# Power.net
KiCad netlist of a schematic drawn in Altium Designer
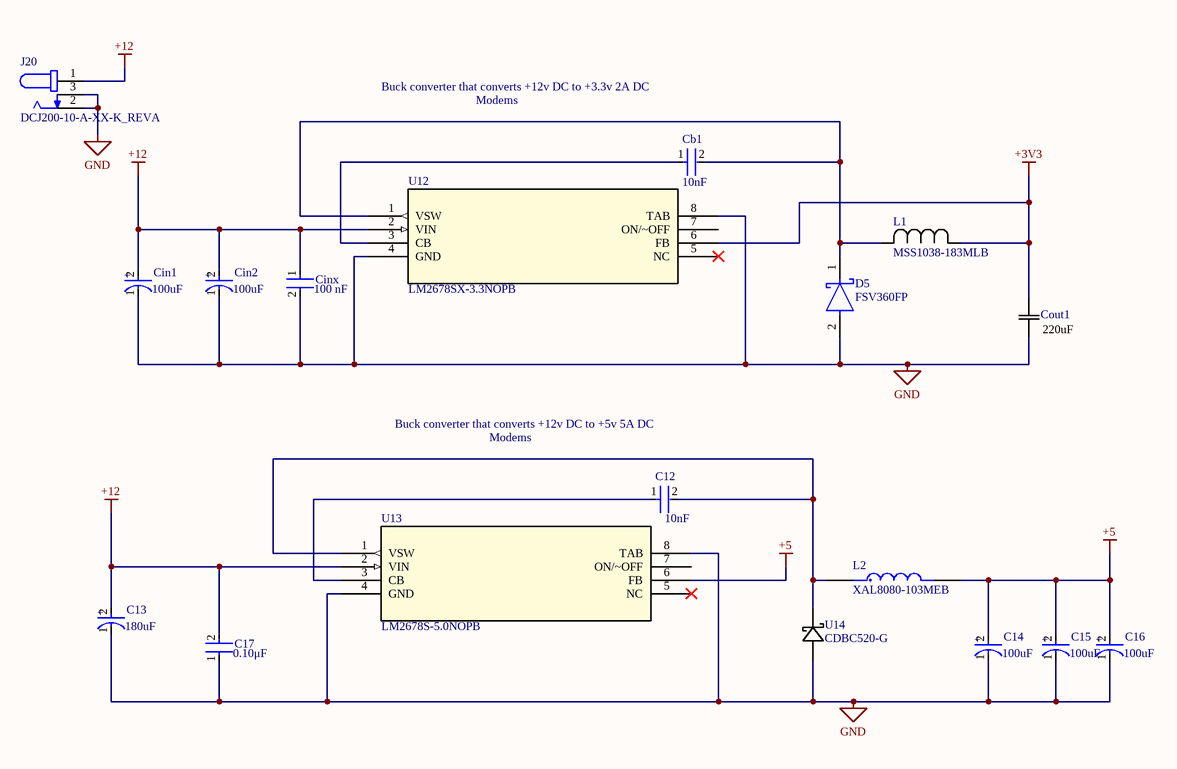
[diagram p0: Power.SchDoc]

(export (version "E")
  (design (tool "Eeschema 10.0.6"))
  (components
    (comp (ref "C12")
      (value "CGA4C2C0G1H103J060AA")
      (footprint "FP-CGA4J-IPC_B")
      (description "Cap Ceramic 10nF 50V C0G 5% Pad SMD 0805 +125°C Automotive T/R")
      (fields (field (name "CAPACITANCE") "10nF") (field (name "TOLERANCE") "5%"))
      (libsource (lib "Altium Content Vault") (part "b4654b650e69147ec39a6b967a45e02"))
    )
    (comp (ref "C13")
      (value "20SVPF180M")
      (footprint "FP-OS-CON-SMT-E7-MFG")
      (description "Conductive Polymer Aluminum Solid Capacitors (OS-CON) 180uF ±20% 20V RADIAL SMT 8x6.9mm")
      (fields
        (field (name "VOLTAGE") "20V")
        (field (name "CAPACITANCE") "180uF")
        (field (name "TOLERANCE") "20%")
      )
      (libsource (lib "Altium Content Vault") (part "cf48714ba7e38822c1575c7ec0b6d1f"))
    )
    (comp (ref "C14")
      (value "8TPE100MAZB")
      (footprint "FP-POSCAP-B2-MFG")
      (description "Molded Tantalum Polymer Capacitor 100uF 20% 8V life 1000Hours SMD 1411")
      (fields
        (field (name "TOLERANCE") "20%")
        (field (name "CAPACITANCE") "100uF")
        (field (name "VOLTAGE") "8V")
      )
      (libsource (lib "Altium Content Vault") (part "cf48714ba7e38822c1575c7ec0b6d1f"))
    )
    (comp (ref "C15")
      (value "8TPE100MAZB")
      (footprint "FP-POSCAP-B2-MFG")
      (description "Molded Tantalum Polymer Capacitor 100uF 20% 8V life 1000Hours SMD 1411")
      (fields
        (field (name "TOLERANCE") "20%")
        (field (name "CAPACITANCE") "100uF")
        (field (name "VOLTAGE") "8V")
      )
      (libsource (lib "Altium Content Vault") (part "cf48714ba7e38822c1575c7ec0b6d1f"))
    )
    (comp (ref "C16")
      (value "8TPE100MAZB")
      (footprint "FP-POSCAP-B2-MFG")
      (description "Molded Tantalum Polymer Capacitor 100uF 20% 8V life 1000Hours SMD 1411")
      (fields
        (field (name "TOLERANCE") "20%")
        (field (name "CAPACITANCE") "100uF")
        (field (name "VOLTAGE") "8V")
      )
      (libsource (lib "Altium Content Vault") (part "cf48714ba7e38822c1575c7ec0b6d1f"))
    )
    (comp (ref "C17")
      (value "GRM155R71C104KA88D")
      (footprint "FP-GRM15-MFG")
      (description "CAP CER 0.1UF 16V X7R 0402")
      (fields
        (field (name "TOLERANCE") "10%")
        (field (name "OCTOPART") "https://octopart.com/grm155r71c104ka88d-murata-196880")
        (field (name "CAPACITANCE") "0.10μF")
      )
      (libsource (lib "Altium Content Vault") (part "236180d848d6139a670b325ea6854c9"))
    )
    (comp (ref "Cb1")
      (value "CGA4C2C0G1H103J060AA")
      (footprint "FP-CGA4J-IPC_B")
      (description "Cap Ceramic 10nF 50V C0G 5% Pad SMD 0805 +125°C Automotive T/R")
      (fields (field (name "CAPACITANCE") "10nF") (field (name "TOLERANCE") "5%"))
      (libsource (lib "Altium Content Vault") (part "b4654b650e69147ec39a6b967a45e02"))
    )
    (comp (ref "Cin1")
      (value "EEE-FK1V101P")
      (footprint "FP-FKF-MFG")
      (description "CAP ALUM 100UF 20% 35V SMD")
      (fields
        (field (name "VOLTAGE") "35V")
        (field (name "CAPACITANCE") "100uF")
        (field (name "TOLERANCE") "20%")
      )
      (libsource (lib "Altium Content Vault") (part "a00bbbee19879c290e62620ae7e47b1"))
    )
    (comp (ref "Cin2")
      (value "EEE-FK1V101P")
      (footprint "FP-FKF-MFG")
      (description "CAP ALUM 100UF 20% 35V SMD")
      (fields
        (field (name "VOLTAGE") "35V")
        (field (name "CAPACITANCE") "100uF")
        (field (name "TOLERANCE") "20%")
      )
      (libsource (lib "Altium Content Vault") (part "a00bbbee19879c290e62620ae7e47b1"))
    )
    (comp (ref "Cinx")
      (value "100 nF")
      (footprint "FP-CC0805-0_85-MFG")
      (description "CAP CER 0.1UF 25V X7R 0805")
      (fields (field (name "MANUFACTURER PART NUMBER") "CC0805KRX7R8BB104") (field (name "TOLERANCE") "0.1"))
      (libsource (lib "Altium Content Vault") (part "11868f565c42a9108669ba33697ecf6"))
    )
    (comp (ref "Cout1")
      (value "220uF")
      (footprint "CHEMI-F61")
      (description "No Description Available")
      (fields (field (name "Comment") "APXF6R3ARA221MF61G"))
      (libsource (lib "APXF6R3ARA221MF61G") (part "APXF6R3ARA221MF61G"))
    )
    (comp (ref "D5")
      (value "FSV360FP")
      (footprint "FP-425AC-MFG")
      (description "DIODE SCHOTTKY 60V 3A SOD123HE")
      (fields
        (field (name "OCTOPART") "https://octopart.com/fsv360fp-on+semiconductor-84328668")
        (field (name "MANUFACTURER") "ON Semiconductor")
      )
      (libsource (lib "Altium Content Vault") (part "1d6ec82d83fb6aee721767c19dac4b9"))
    )
    (comp (ref "J20")
      (value "DCJ200-10-A-XX-K_REVA")
      (footprint "GCT_DCJ200-10-A-XX-K_REVA")
      (description "Power Barrel Connector Jack 2.05mm ID (0.081), 5.50mm OD (0.217) Through Hole, Right Angle")
      (fields (field (name "MF") "Global Connector Technology") (field (name "MP") "DCJ200-10-A-K1-K"))
      (libsource (lib "DCJ200-10-A-XX-K_REVA") (part "DCJ200-10-A-XX-K_REVA"))
    )
    (comp (ref "L1")
      (value "MSS1038-183MLB")
      (footprint "IND_MSS1038_COC")
      (description "No Description Available")
      (libsource (lib "MSS1038-183MLB") (part "MSS1038-183MLB"))
    )
    (comp (ref "L2")
      (value "XAL8080-103MEB")
      (footprint "IND_XAL8080-103MEB")
      (libsource (lib "XAL8080-103MEB") (part "XAL8080-103MEB"))
    )
    (comp (ref "U12")
      (value "LM2678SX-3.3NOPB")
      (footprint "TS7B")
      (description "No Description Available")
      (libsource (lib "LM2678SX-3P3NOPB") (part "LM2678SX-3.3NOPB"))
    )
    (comp (ref "U13")
      (value "LM2678S-5.0NOPB")
      (footprint "TS7B")
      (description "No Description Available")
      (libsource (lib "LM2678S-5P0NOPB") (part "LM2678S-5.0NOPB"))
    )
    (comp (ref "U14")
      (value "CDBC520-G")
      (footprint "CDBC-G")
      (description "No Description Available")
      (libsource (lib "CDBC520-G") (part "CDBC520-G"))
    )
  )
  (nets
    (net (code "1") (name "+3V3") (class "Default")
      (node (ref "Cout1") (pin "2") (pinfunction "2_2") (pintype "passive"))
      (node (ref "L1") (pin "1") (pinfunction "1_1") (pintype "passive"))
      (node (ref "U12") (pin "6") (pinfunction "FB_6") (pintype "passive"))
    )
    (net (code "2") (name "+5") (class "Default")
      (node (ref "C14") (pin "2") (pinfunction "A_2") (pintype "passive"))
      (node (ref "C15") (pin "2") (pinfunction "A_2") (pintype "passive"))
      (node (ref "C16") (pin "2") (pinfunction "A_2") (pintype "passive"))
      (node (ref "L2") (pin "2") (pinfunction "2_2") (pintype "passive"))
      (node (ref "U13") (pin "6") (pinfunction "FB_6") (pintype "passive"))
    )
    (net (code "3") (name "+12") (class "Default")
      (node (ref "C13") (pin "2") (pinfunction "A_2") (pintype "passive"))
      (node (ref "C17") (pin "2") (pinfunction "2_2") (pintype "passive"))
      (node (ref "Cin1") (pin "2") (pinfunction "A_2") (pintype "passive"))
      (node (ref "Cin2") (pin "2") (pinfunction "A_2") (pintype "passive"))
      (node (ref "Cinx") (pin "1") (pinfunction "1_1") (pintype "passive"))
      (node (ref "J20") (pin "1") (pinfunction "1_1") (pintype "power_in"))
      (node (ref "U12") (pin "2") (pinfunction "VIN_2") (pintype "input"))
      (node (ref "U13") (pin "2") (pinfunction "VIN_2") (pintype "input"))
    )
    (net (code "4") (name "GND") (class "Default")
      (node (ref "C13") (pin "1") (pinfunction "C_1") (pintype "passive"))
      (node (ref "C14") (pin "1") (pinfunction "C_1") (pintype "passive"))
      (node (ref "C15") (pin "1") (pinfunction "C_1") (pintype "passive"))
      (node (ref "C16") (pin "1") (pinfunction "C_1") (pintype "passive"))
      (node (ref "C17") (pin "1") (pinfunction "1_1") (pintype "passive"))
      (node (ref "Cin1") (pin "1") (pinfunction "C_1") (pintype "passive"))
      (node (ref "Cin2") (pin "1") (pinfunction "C_1") (pintype "passive"))
      (node (ref "Cinx") (pin "2") (pinfunction "2_2") (pintype "passive"))
      (node (ref "Cout1") (pin "1") (pinfunction "1_1") (pintype "passive"))
      (node (ref "D5") (pin "2") (pinfunction "A_2") (pintype "passive"))
      (node (ref "J20") (pin "2") (pinfunction "2_2") (pintype "passive"))
      (node (ref "J20") (pin "3") (pinfunction "3_3") (pintype "passive"))
      (node (ref "U12") (pin "4") (pinfunction "GND_4") (pintype "passive"))
      (node (ref "U12") (pin "8") (pinfunction "TAB_8") (pintype "passive"))
      (node (ref "U13") (pin "4") (pinfunction "GND_4") (pintype "passive"))
      (node (ref "U13") (pin "8") (pinfunction "TAB_8") (pintype "passive"))
      (node (ref "U14") (pin "2") (pinfunction "2_2") (pintype "passive"))
    )
    (net (code "5") (name "Net-(D5-C)") (class "Default")
      (node (ref "Cb1") (pin "2") (pinfunction "2_2") (pintype "passive"))
      (node (ref "D5") (pin "1") (pinfunction "C_1") (pintype "passive"))
      (node (ref "L1") (pin "2") (pinfunction "2_2") (pintype "passive"))
      (node (ref "U12") (pin "1") (pinfunction "VSW_1") (pintype "output"))
    )
    (net (code "6") (name "Net-(U12-CB)") (class "Default")
      (node (ref "Cb1") (pin "1") (pinfunction "1_1") (pintype "passive"))
      (node (ref "U12") (pin "3") (pinfunction "CB_3") (pintype "passive"))
    )
    (net (code "7") (name "Net-(U13-CB)") (class "Default")
      (node (ref "C12") (pin "1") (pinfunction "1_1") (pintype "passive"))
      (node (ref "U13") (pin "3") (pinfunction "CB_3") (pintype "passive"))
    )
    (net (code "8") (name "Net-(U13-VSW)") (class "Default")
      (node (ref "C12") (pin "2") (pinfunction "2_2") (pintype "passive"))
      (node (ref "L2") (pin "1") (pinfunction "1_1") (pintype "passive"))
      (node (ref "U13") (pin "1") (pinfunction "VSW_1") (pintype "output"))
      (node (ref "U14") (pin "1") (pinfunction "1_1") (pintype "passive"))
    )
    (net (code "9") (name "unconnected-(U12-NC-Pad5)") (class "Default")
      (node (ref "U12") (pin "5") (pinfunction "NC_5") (pintype "passive+no_connect"))
    )
    (net (code "10") (name "unconnected-(U12-ON{slash}~OFF-Pad7)") (class "Default")
      (node (ref "U12") (pin "7") (pinfunction "ON/~OFF_7") (pintype "passive"))
    )
    (net (code "11") (name "unconnected-(U13-NC-Pad5)") (class "Default")
      (node (ref "U13") (pin "5") (pinfunction "NC_5") (pintype "passive+no_connect"))
    )
    (net (code "12") (name "unconnected-(U13-ON{slash}~OFF-Pad7)") (class "Default")
      (node (ref "U13") (pin "7") (pinfunction "ON/~OFF_7") (pintype "passive"))
    )
  )
)
